# Camera.net
KiCad netlist of a schematic drawn in EAGLE
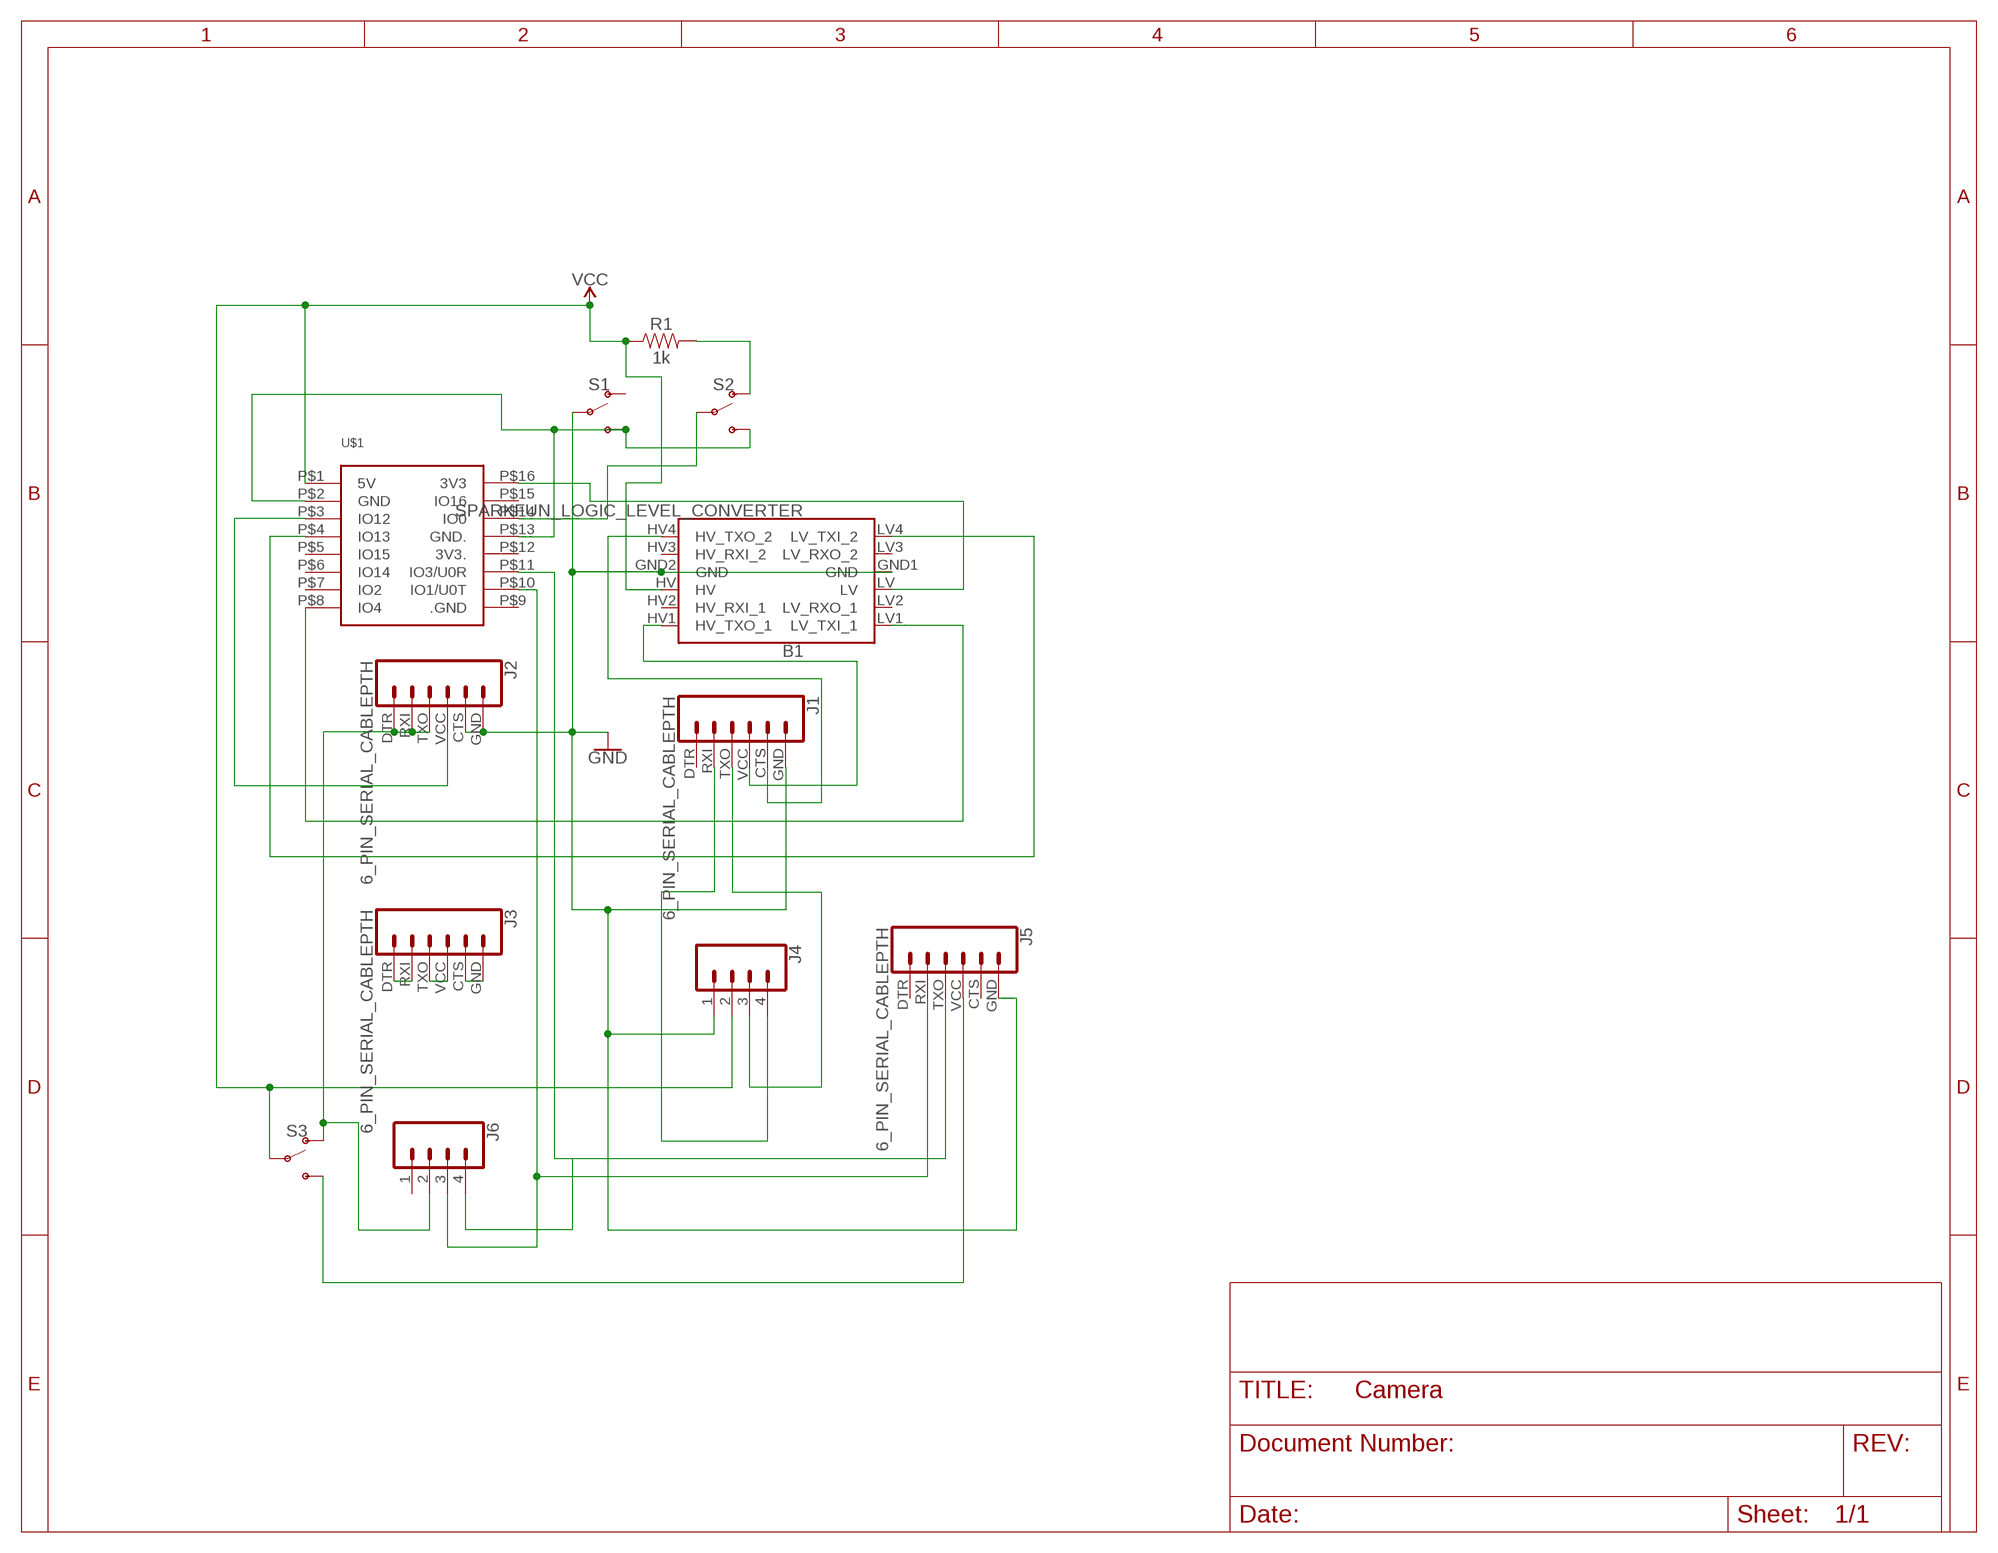
[diagram p0: schematic, sheet 1]

(export (version "E")
  (design (tool "Eeschema 10.0.6"))
  (components
    (comp (ref "B1")
      (value "SPARKFUN_LOGIC_LEVEL_CONVERTER")
      (footprint "eagle-import:SPARKFUN_LOGIC_LEVEL_CONVERTER")
      (libsource (lib "eagle-import") (part "SPARKFUN_LOGIC_LEVEL_CONVERTER"))
    )
    (comp (ref "J1")
      (value "6_PIN_SERIAL_CABLEPTH")
      (footprint "eagle-import:FTDI_BASIC")
      (libsource (lib "eagle-import") (part "6_PIN_SERIAL_CABLEPTH"))
    )
    (comp (ref "J2")
      (value "6_PIN_SERIAL_CABLEPTH")
      (footprint "eagle-import:FTDI_BASIC")
      (libsource (lib "eagle-import") (part "6_PIN_SERIAL_CABLEPTH"))
    )
    (comp (ref "J3")
      (value "6_PIN_SERIAL_CABLEPTH")
      (footprint "eagle-import:FTDI_BASIC")
      (libsource (lib "eagle-import") (part "6_PIN_SERIAL_CABLEPTH"))
    )
    (comp (ref "J4")
      (value "CONN_04PTH")
      (footprint "eagle-import:1X04")
      (libsource (lib "eagle-import") (part "CONN_04PTH"))
    )
    (comp (ref "J5")
      (value "6_PIN_SERIAL_CABLEPTH")
      (footprint "eagle-import:FTDI_BASIC")
      (libsource (lib "eagle-import") (part "6_PIN_SERIAL_CABLEPTH"))
    )
    (comp (ref "J6")
      (value "CONN_04PTH")
      (footprint "eagle-import:1X04")
      (libsource (lib "eagle-import") (part "CONN_04PTH"))
    )
    (comp (ref "R1")
      (value "1k")
      (footprint "eagle-import:AXIAL-0.3-KIT")
      (libsource (lib "eagle-import") (part "1KOHM-HORIZ_KIT-1/4W-1%"))
    )
    (comp (ref "S1")
      (value "SWITCH-SPDT-PTH-11.6X4.0MM")
      (footprint "eagle-import:SWITCH_SPDT_PTH_11.6X4.0MM")
      (libsource (lib "eagle-import") (part "SWITCH-SPDT-PTH-11.6X4.0MM"))
    )
    (comp (ref "S2")
      (value "SWITCH-SPDT-PTH-11.6X4.0MM")
      (footprint "eagle-import:SWITCH_SPDT_PTH_11.6X4.0MM")
      (libsource (lib "eagle-import") (part "SWITCH-SPDT-PTH-11.6X4.0MM"))
    )
    (comp (ref "S3")
      (value "SWITCH-SPDT-PTH-11.6X4.0MM")
      (footprint "eagle-import:SWITCH_SPDT_PTH_11.6X4.0MM")
      (libsource (lib "eagle-import") (part "SWITCH-SPDT-PTH-11.6X4.0MM"))
    )
    (comp (ref "U$1")
      (value "ESP32-CAM")
      (footprint "eagle-import:ESP32-CAM")
      (fields (field (name "MF") "AI-Thinker"))
      (libsource (lib "eagle-import") (part "ESP32-CAM"))
    )
  )
  (nets
    (net (code "1") (name "GND") (class "Default")
      (node (ref "B1") (pin "GND1") (pinfunction "GND_GND1") (pintype "power_in"))
      (node (ref "B1") (pin "GND2") (pinfunction "GND_GND2") (pintype "power_in"))
      (node (ref "J1") (pin "GND") (pinfunction "6_GND") (pintype "passive"))
      (node (ref "J2") (pin "CTS") (pinfunction "5_CTS") (pintype "passive"))
      (node (ref "J2") (pin "GND") (pinfunction "6_GND") (pintype "passive"))
      (node (ref "J4") (pin "1") (pinfunction "1_1") (pintype "passive"))
      (node (ref "J5") (pin "GND") (pinfunction "6_GND") (pintype "passive"))
      (node (ref "S1") (pin "2") (pinfunction "P_2") (pintype "passive"))
    )
    (net (code "2") (name "Net-(B1-HV_TXO_1)") (class "Default")
      (node (ref "B1") (pin "HV1") (pinfunction "HV_TXO_1_HV1") (pintype "bidirectional"))
      (node (ref "J1") (pin "VCC") (pinfunction "4_VCC") (pintype "passive"))
    )
    (net (code "3") (name "Net-(B1-HV_TXO_2)") (class "Default")
      (node (ref "B1") (pin "HV4") (pinfunction "HV_TXO_2_HV4") (pintype "bidirectional"))
      (node (ref "J1") (pin "CTS") (pinfunction "5_CTS") (pintype "passive"))
    )
    (net (code "4") (name "Net-(B1-LV_TXI_1)") (class "Default")
      (node (ref "B1") (pin "LV1") (pinfunction "LV_TXI_1_LV1") (pintype "bidirectional"))
      (node (ref "U$1") (pin "P$8") (pinfunction "IO4_P$8") (pintype "bidirectional"))
    )
    (net (code "5") (name "Net-(B1-LV_TXI_2)") (class "Default")
      (node (ref "B1") (pin "LV4") (pinfunction "LV_TXI_2_LV4") (pintype "bidirectional"))
      (node (ref "U$1") (pin "P$4") (pinfunction "IO13_P$4") (pintype "bidirectional"))
    )
    (net (code "6") (name "Net-(J1-2)") (class "Default")
      (node (ref "J1") (pin "RXI") (pinfunction "2_RXI") (pintype "passive"))
      (node (ref "J4") (pin "4") (pinfunction "4_4") (pintype "passive"))
    )
    (net (code "7") (name "Net-(J1-3)") (class "Default")
      (node (ref "J1") (pin "TXO") (pinfunction "3_TXO") (pintype "passive"))
      (node (ref "J4") (pin "3") (pinfunction "3_3") (pintype "passive"))
    )
    (net (code "8") (name "Net-(J2-1)") (class "Default")
      (node (ref "J2") (pin "DTR") (pinfunction "1_DTR") (pintype "passive"))
      (node (ref "J2") (pin "RXI") (pinfunction "2_RXI") (pintype "passive"))
      (node (ref "J2") (pin "TXO") (pinfunction "3_TXO") (pintype "passive"))
      (node (ref "J6") (pin "2") (pinfunction "2_2") (pintype "passive"))
      (node (ref "S3") (pin "1") (pinfunction "O_1") (pintype "passive"))
    )
    (net (code "9") (name "Net-(J2-4)") (class "Default")
      (node (ref "J2") (pin "VCC") (pinfunction "4_VCC") (pintype "passive"))
      (node (ref "U$1") (pin "P$3") (pinfunction "IO12_P$3") (pintype "bidirectional"))
    )
    (net (code "10") (name "Net-(J3-1)") (class "Default")
      (node (ref "J3") (pin "DTR") (pinfunction "1_DTR") (pintype "passive"))
      (node (ref "J3") (pin "RXI") (pinfunction "2_RXI") (pintype "passive"))
    )
    (net (code "11") (name "Net-(J3-3)") (class "Default")
      (node (ref "J3") (pin "TXO") (pinfunction "3_TXO") (pintype "passive"))
      (node (ref "J3") (pin "VCC") (pinfunction "4_VCC") (pintype "passive"))
    )
    (net (code "12") (name "Net-(J3-5)") (class "Default")
      (node (ref "J3") (pin "CTS") (pinfunction "5_CTS") (pintype "passive"))
      (node (ref "J3") (pin "GND") (pinfunction "6_GND") (pintype "passive"))
    )
    (net (code "13") (name "Net-(J5-2)") (class "Default")
      (node (ref "J5") (pin "RXI") (pinfunction "2_RXI") (pintype "passive"))
      (node (ref "J6") (pin "3") (pinfunction "3_3") (pintype "passive"))
      (node (ref "U$1") (pin "P$10") (pinfunction "IO1/U0T_P$10") (pintype "bidirectional"))
    )
    (net (code "14") (name "Net-(J5-3)") (class "Default")
      (node (ref "J5") (pin "TXO") (pinfunction "3_TXO") (pintype "passive"))
      (node (ref "J6") (pin "4") (pinfunction "4_4") (pintype "passive"))
      (node (ref "U$1") (pin "P$11") (pinfunction "IO3/U0R_P$11") (pintype "bidirectional"))
    )
    (net (code "15") (name "Net-(J5-4)") (class "Default")
      (node (ref "J5") (pin "VCC") (pinfunction "4_VCC") (pintype "passive"))
      (node (ref "S3") (pin "3") (pinfunction "S_3") (pintype "passive"))
    )
    (net (code "16") (name "Net-(R1-2)") (class "Default")
      (node (ref "R1") (pin "P$2") (pinfunction "2_P$2") (pintype "passive"))
      (node (ref "S2") (pin "1") (pinfunction "O_1") (pintype "passive"))
    )
    (net (code "17") (name "Net-(S1-S)") (class "Default")
      (node (ref "S1") (pin "3") (pinfunction "S_3") (pintype "passive"))
      (node (ref "S2") (pin "3") (pinfunction "S_3") (pintype "passive"))
      (node (ref "U$1") (pin "P$13") (pinfunction "GND._P$13") (pintype "bidirectional"))
      (node (ref "U$1") (pin "P$2") (pinfunction "GND_P$2") (pintype "bidirectional"))
    )
    (net (code "18") (name "Net-(S2-P)") (class "Default")
      (node (ref "S2") (pin "2") (pinfunction "P_2") (pintype "passive"))
      (node (ref "U$1") (pin "P$14") (pinfunction "IO0_P$14") (pintype "bidirectional"))
    )
    (net (code "19") (name "Net-(U$1-3V3)") (class "Default")
      (node (ref "B1") (pin "LV") (pinfunction "LV_LV") (pintype "power_in"))
      (node (ref "U$1") (pin "P$16") (pinfunction "3V3_P$16") (pintype "bidirectional"))
    )
    (net (code "20") (name "VCC") (class "Default")
      (node (ref "B1") (pin "HV") (pinfunction "HV_HV") (pintype "power_in"))
      (node (ref "J4") (pin "2") (pinfunction "2_2") (pintype "passive"))
      (node (ref "R1") (pin "P$1") (pinfunction "1_P$1") (pintype "passive"))
      (node (ref "S3") (pin "2") (pinfunction "P_2") (pintype "passive"))
      (node (ref "U$1") (pin "P$1") (pinfunction "5V_P$1") (pintype "bidirectional"))
    )
    (net (code "21") (name "unconnected-(B1-HV_RXI_1-PadHV2)") (class "Default")
      (node (ref "B1") (pin "HV2") (pinfunction "HV_RXI_1_HV2") (pintype "bidirectional"))
    )
    (net (code "22") (name "unconnected-(B1-HV_RXI_2-PadHV3)") (class "Default")
      (node (ref "B1") (pin "HV3") (pinfunction "HV_RXI_2_HV3") (pintype "bidirectional"))
    )
    (net (code "23") (name "unconnected-(B1-LV_RXO_1-PadLV2)") (class "Default")
      (node (ref "B1") (pin "LV2") (pinfunction "LV_RXO_1_LV2") (pintype "bidirectional"))
    )
    (net (code "24") (name "unconnected-(B1-LV_RXO_2-PadLV3)") (class "Default")
      (node (ref "B1") (pin "LV3") (pinfunction "LV_RXO_2_LV3") (pintype "bidirectional"))
    )
    (net (code "25") (name "unconnected-(J1-1-PadDTR)") (class "Default")
      (node (ref "J1") (pin "DTR") (pinfunction "1_DTR") (pintype "passive"))
    )
    (net (code "26") (name "unconnected-(J5-1-PadDTR)") (class "Default")
      (node (ref "J5") (pin "DTR") (pinfunction "1_DTR") (pintype "passive"))
    )
    (net (code "27") (name "unconnected-(J5-5-PadCTS)") (class "Default")
      (node (ref "J5") (pin "CTS") (pinfunction "5_CTS") (pintype "passive"))
    )
    (net (code "28") (name "unconnected-(J6-Pad1)") (class "Default")
      (node (ref "J6") (pin "1") (pinfunction "1_1") (pintype "passive"))
    )
    (net (code "29") (name "unconnected-(S1-O-Pad1)") (class "Default")
      (node (ref "S1") (pin "1") (pinfunction "O_1") (pintype "passive"))
    )
    (net (code "30") (name "unconnected-(U$1-.GND-PadP$9)") (class "Default")
      (node (ref "U$1") (pin "P$9") (pinfunction ".GND_P$9") (pintype "bidirectional"))
    )
    (net (code "31") (name "unconnected-(U$1-3V3.-PadP$12)") (class "Default")
      (node (ref "U$1") (pin "P$12") (pinfunction "3V3._P$12") (pintype "bidirectional"))
    )
    (net (code "32") (name "unconnected-(U$1-IO2-PadP$7)") (class "Default")
      (node (ref "U$1") (pin "P$7") (pinfunction "IO2_P$7") (pintype "bidirectional"))
    )
    (net (code "33") (name "unconnected-(U$1-IO14-PadP$6)") (class "Default")
      (node (ref "U$1") (pin "P$6") (pinfunction "IO14_P$6") (pintype "bidirectional"))
    )
    (net (code "34") (name "unconnected-(U$1-IO15-PadP$5)") (class "Default")
      (node (ref "U$1") (pin "P$5") (pinfunction "IO15_P$5") (pintype "bidirectional"))
    )
    (net (code "35") (name "unconnected-(U$1-IO16-PadP$15)") (class "Default")
      (node (ref "U$1") (pin "P$15") (pinfunction "IO16_P$15") (pintype "bidirectional"))
    )
  )
)
